# Camera_Ribbon.net
KiCad netlist of a schematic drawn in Altium Designer
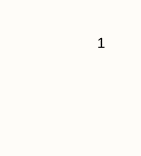
[diagram p0: Camera_Ribbon.SchDoc, top right]
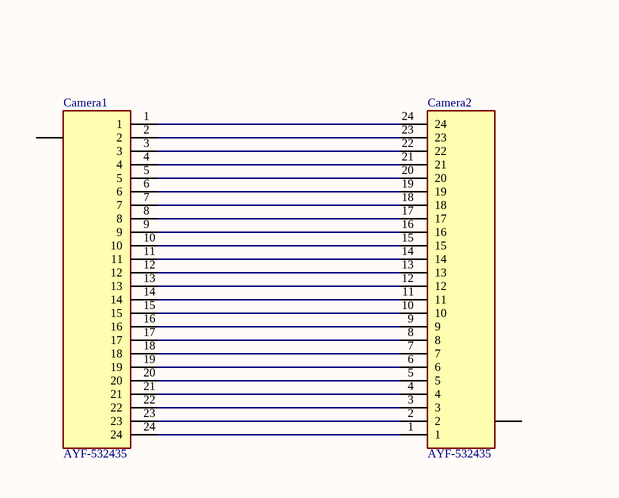
[diagram p1: Camera_Ribbon.SchDoc, bottom left]

(export (version "E")
  (design (tool "Eeschema 10.0.6"))
  (components
    (comp (ref "Camera1")
      (value "AYF-532435")
      (footprint "FPC-SMD_24P-P0.50_L6.4-W15.1")
      (description "Connector")
      (libsource (lib "") (part "AYF-532435_1"))
    )
    (comp (ref "Camera2")
      (value "AYF-532435")
      (footprint "FPC-SMD_24P-P0.50_L6.4-W15.1")
      (description "Connector")
      (libsource (lib "*") (part "AYF-532435"))
    )
  )
  (nets
    (net (code "1") (name "Net-(Camera1-Pad1)") (class "Default")
      (node (ref "Camera1") (pin "1") (pinfunction "1_1") (pintype "passive"))
      (node (ref "Camera2") (pin "24") (pinfunction "24_24") (pintype "passive"))
    )
    (net (code "2") (name "Net-(Camera1-Pad2)") (class "Default")
      (node (ref "Camera1") (pin "2") (pinfunction "2_2") (pintype "passive"))
      (node (ref "Camera2") (pin "23") (pinfunction "23_23") (pintype "passive"))
    )
    (net (code "3") (name "Net-(Camera1-Pad3)") (class "Default")
      (node (ref "Camera1") (pin "3") (pinfunction "3_3") (pintype "passive"))
      (node (ref "Camera2") (pin "22") (pinfunction "22_22") (pintype "passive"))
    )
    (net (code "4") (name "Net-(Camera1-Pad4)") (class "Default")
      (node (ref "Camera1") (pin "4") (pinfunction "4_4") (pintype "passive"))
      (node (ref "Camera2") (pin "21") (pinfunction "21_21") (pintype "passive"))
    )
    (net (code "5") (name "Net-(Camera1-Pad5)") (class "Default")
      (node (ref "Camera1") (pin "5") (pinfunction "5_5") (pintype "passive"))
      (node (ref "Camera2") (pin "20") (pinfunction "20_20") (pintype "passive"))
    )
    (net (code "6") (name "Net-(Camera1-Pad6)") (class "Default")
      (node (ref "Camera1") (pin "6") (pinfunction "6_6") (pintype "passive"))
      (node (ref "Camera2") (pin "19") (pinfunction "19_19") (pintype "passive"))
    )
    (net (code "7") (name "Net-(Camera1-Pad7)") (class "Default")
      (node (ref "Camera1") (pin "7") (pinfunction "7_7") (pintype "passive"))
      (node (ref "Camera2") (pin "18") (pinfunction "18_18") (pintype "passive"))
    )
    (net (code "8") (name "Net-(Camera1-Pad8)") (class "Default")
      (node (ref "Camera1") (pin "8") (pinfunction "8_8") (pintype "passive"))
      (node (ref "Camera2") (pin "17") (pinfunction "17_17") (pintype "passive"))
    )
    (net (code "9") (name "Net-(Camera1-Pad9)") (class "Default")
      (node (ref "Camera1") (pin "9") (pinfunction "9_9") (pintype "passive"))
      (node (ref "Camera2") (pin "16") (pinfunction "16_16") (pintype "passive"))
    )
    (net (code "10") (name "Net-(Camera1-Pad10)") (class "Default")
      (node (ref "Camera1") (pin "10") (pinfunction "10_10") (pintype "passive"))
      (node (ref "Camera2") (pin "15") (pinfunction "15_15") (pintype "passive"))
    )
    (net (code "11") (name "Net-(Camera1-Pad11)") (class "Default")
      (node (ref "Camera1") (pin "11") (pinfunction "11_11") (pintype "passive"))
      (node (ref "Camera2") (pin "14") (pinfunction "14_14") (pintype "passive"))
    )
    (net (code "12") (name "Net-(Camera1-Pad12)") (class "Default")
      (node (ref "Camera1") (pin "12") (pinfunction "12_12") (pintype "passive"))
      (node (ref "Camera2") (pin "13") (pinfunction "13_13") (pintype "passive"))
    )
    (net (code "13") (name "Net-(Camera1-Pad13)") (class "Default")
      (node (ref "Camera1") (pin "13") (pinfunction "13_13") (pintype "passive"))
      (node (ref "Camera2") (pin "12") (pinfunction "12_12") (pintype "passive"))
    )
    (net (code "14") (name "Net-(Camera1-Pad14)") (class "Default")
      (node (ref "Camera1") (pin "14") (pinfunction "14_14") (pintype "passive"))
      (node (ref "Camera2") (pin "11") (pinfunction "11_11") (pintype "passive"))
    )
    (net (code "15") (name "Net-(Camera1-Pad15)") (class "Default")
      (node (ref "Camera1") (pin "15") (pinfunction "15_15") (pintype "passive"))
      (node (ref "Camera2") (pin "10") (pinfunction "10_10") (pintype "passive"))
    )
    (net (code "16") (name "Net-(Camera1-Pad16)") (class "Default")
      (node (ref "Camera1") (pin "16") (pinfunction "16_16") (pintype "passive"))
      (node (ref "Camera2") (pin "9") (pinfunction "9_9") (pintype "passive"))
    )
    (net (code "17") (name "Net-(Camera1-Pad17)") (class "Default")
      (node (ref "Camera1") (pin "17") (pinfunction "17_17") (pintype "passive"))
      (node (ref "Camera2") (pin "8") (pinfunction "8_8") (pintype "passive"))
    )
    (net (code "18") (name "Net-(Camera1-Pad18)") (class "Default")
      (node (ref "Camera1") (pin "18") (pinfunction "18_18") (pintype "passive"))
      (node (ref "Camera2") (pin "7") (pinfunction "7_7") (pintype "passive"))
    )
    (net (code "19") (name "Net-(Camera1-Pad19)") (class "Default")
      (node (ref "Camera1") (pin "19") (pinfunction "19_19") (pintype "passive"))
      (node (ref "Camera2") (pin "6") (pinfunction "6_6") (pintype "passive"))
    )
    (net (code "20") (name "Net-(Camera1-Pad20)") (class "Default")
      (node (ref "Camera1") (pin "20") (pinfunction "20_20") (pintype "passive"))
      (node (ref "Camera2") (pin "5") (pinfunction "5_5") (pintype "passive"))
    )
    (net (code "21") (name "Net-(Camera1-Pad21)") (class "Default")
      (node (ref "Camera1") (pin "21") (pinfunction "21_21") (pintype "passive"))
      (node (ref "Camera2") (pin "4") (pinfunction "4_4") (pintype "passive"))
    )
    (net (code "22") (name "Net-(Camera1-Pad22)") (class "Default")
      (node (ref "Camera1") (pin "22") (pinfunction "22_22") (pintype "passive"))
      (node (ref "Camera2") (pin "3") (pinfunction "3_3") (pintype "passive"))
    )
    (net (code "23") (name "Net-(Camera1-Pad23)") (class "Default")
      (node (ref "Camera1") (pin "23") (pinfunction "23_23") (pintype "passive"))
      (node (ref "Camera2") (pin "2") (pinfunction "2_2") (pintype "passive"))
    )
    (net (code "24") (name "Net-(Camera1-Pad24)") (class "Default")
      (node (ref "Camera1") (pin "24") (pinfunction "24_24") (pintype "passive"))
      (node (ref "Camera2") (pin "1") (pinfunction "1_1") (pintype "passive"))
    )
    (net (code "25") (name "unconnected-(Camera1-Pad0)") (class "Default")
      (node (ref "Camera1") (pin "0") (pinfunction "0_0") (pintype "passive"))
    )
    (net (code "26") (name "unconnected-(Camera2-Pad0)") (class "Default")
      (node (ref "Camera2") (pin "0") (pinfunction "0_0") (pintype "passive"))
    )
  )
)
